# Switches.net
KiCad netlist of a schematic drawn in Altium Designer
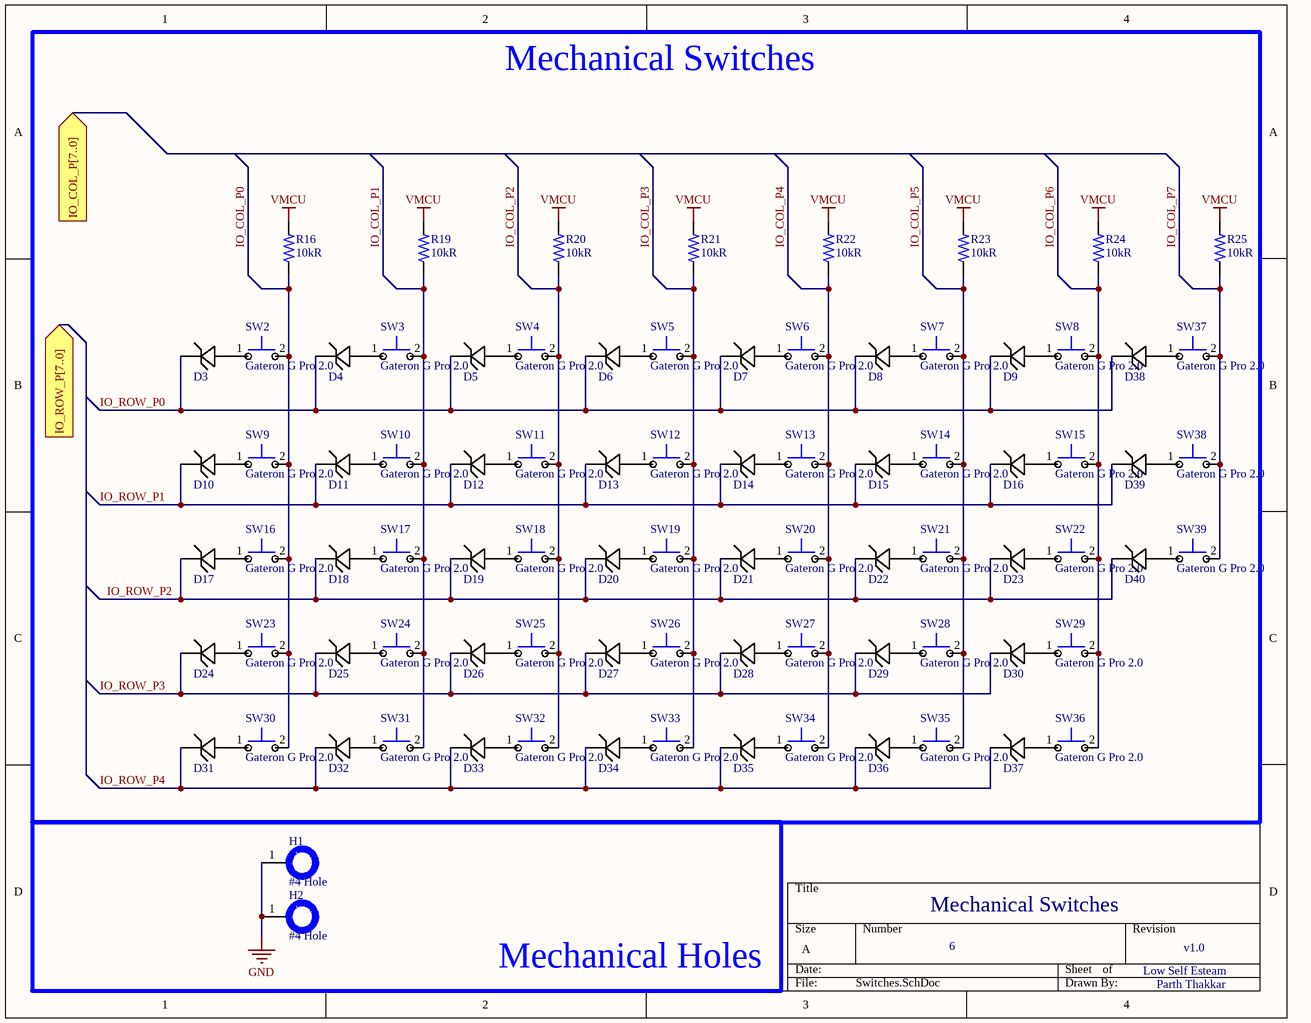
[diagram p0: Switches.SchDoc]

(export (version "E")
  (design (tool "Eeschema 10.0.6"))
  (components
    (comp (ref "D3")
      (value "Diode Schottky")
      (footprint "Diode Schottky")
      (description "Rectifier Diode, Schottky, 2 Element, 0.2A, 30V V(RRM), Silicon")
      (fields (field (name "MANUFACTURER") "Good-Ark") (field (name "MANUFACTURER PART NUMBER") "BAT54C"))
      (libsource (lib "Keyboard_parts") (part "Diode Schottky"))
    )
    (comp (ref "D4")
      (value "Diode Schottky")
      (footprint "Diode Schottky")
      (description "Rectifier Diode, Schottky, 2 Element, 0.2A, 30V V(RRM), Silicon")
      (fields (field (name "MANUFACTURER") "Good-Ark") (field (name "MANUFACTURER PART NUMBER") "BAT54C"))
      (libsource (lib "Keyboard_parts") (part "Diode Schottky"))
    )
    (comp (ref "D5")
      (value "Diode Schottky")
      (footprint "Diode Schottky")
      (description "Rectifier Diode, Schottky, 2 Element, 0.2A, 30V V(RRM), Silicon")
      (fields (field (name "MANUFACTURER") "Good-Ark") (field (name "MANUFACTURER PART NUMBER") "BAT54C"))
      (libsource (lib "Keyboard_parts") (part "Diode Schottky"))
    )
    (comp (ref "D6")
      (value "Diode Schottky")
      (footprint "Diode Schottky")
      (description "Rectifier Diode, Schottky, 2 Element, 0.2A, 30V V(RRM), Silicon")
      (fields (field (name "MANUFACTURER") "Good-Ark") (field (name "MANUFACTURER PART NUMBER") "BAT54C"))
      (libsource (lib "Keyboard_parts") (part "Diode Schottky"))
    )
    (comp (ref "D7")
      (value "Diode Schottky")
      (footprint "Diode Schottky")
      (description "Rectifier Diode, Schottky, 2 Element, 0.2A, 30V V(RRM), Silicon")
      (fields (field (name "MANUFACTURER") "Good-Ark") (field (name "MANUFACTURER PART NUMBER") "BAT54C"))
      (libsource (lib "Keyboard_parts") (part "Diode Schottky"))
    )
    (comp (ref "D8")
      (value "Diode Schottky")
      (footprint "Diode Schottky")
      (description "Rectifier Diode, Schottky, 2 Element, 0.2A, 30V V(RRM), Silicon")
      (fields (field (name "MANUFACTURER") "Good-Ark") (field (name "MANUFACTURER PART NUMBER") "BAT54C"))
      (libsource (lib "Keyboard_parts") (part "Diode Schottky"))
    )
    (comp (ref "D9")
      (value "Diode Schottky")
      (footprint "Diode Schottky")
      (description "Rectifier Diode, Schottky, 2 Element, 0.2A, 30V V(RRM), Silicon")
      (fields (field (name "MANUFACTURER") "Good-Ark") (field (name "MANUFACTURER PART NUMBER") "BAT54C"))
      (libsource (lib "Keyboard_parts") (part "Diode Schottky"))
    )
    (comp (ref "D10")
      (value "Diode Schottky")
      (footprint "Diode Schottky")
      (description "Rectifier Diode, Schottky, 2 Element, 0.2A, 30V V(RRM), Silicon")
      (fields (field (name "MANUFACTURER") "Good-Ark") (field (name "MANUFACTURER PART NUMBER") "BAT54C"))
      (libsource (lib "Keyboard_parts") (part "Diode Schottky"))
    )
    (comp (ref "D11")
      (value "Diode Schottky")
      (footprint "Diode Schottky")
      (description "Rectifier Diode, Schottky, 2 Element, 0.2A, 30V V(RRM), Silicon")
      (fields (field (name "MANUFACTURER") "Good-Ark") (field (name "MANUFACTURER PART NUMBER") "BAT54C"))
      (libsource (lib "Keyboard_parts") (part "Diode Schottky"))
    )
    (comp (ref "D12")
      (value "Diode Schottky")
      (footprint "Diode Schottky")
      (description "Rectifier Diode, Schottky, 2 Element, 0.2A, 30V V(RRM), Silicon")
      (fields (field (name "MANUFACTURER") "Good-Ark") (field (name "MANUFACTURER PART NUMBER") "BAT54C"))
      (libsource (lib "Keyboard_parts") (part "Diode Schottky"))
    )
    (comp (ref "D13")
      (value "Diode Schottky")
      (footprint "Diode Schottky")
      (description "Rectifier Diode, Schottky, 2 Element, 0.2A, 30V V(RRM), Silicon")
      (fields (field (name "MANUFACTURER") "Good-Ark") (field (name "MANUFACTURER PART NUMBER") "BAT54C"))
      (libsource (lib "Keyboard_parts") (part "Diode Schottky"))
    )
    (comp (ref "D14")
      (value "Diode Schottky")
      (footprint "Diode Schottky")
      (description "Rectifier Diode, Schottky, 2 Element, 0.2A, 30V V(RRM), Silicon")
      (fields (field (name "MANUFACTURER") "Good-Ark") (field (name "MANUFACTURER PART NUMBER") "BAT54C"))
      (libsource (lib "Keyboard_parts") (part "Diode Schottky"))
    )
    (comp (ref "D15")
      (value "Diode Schottky")
      (footprint "Diode Schottky")
      (description "Rectifier Diode, Schottky, 2 Element, 0.2A, 30V V(RRM), Silicon")
      (fields (field (name "MANUFACTURER") "Good-Ark") (field (name "MANUFACTURER PART NUMBER") "BAT54C"))
      (libsource (lib "Keyboard_parts") (part "Diode Schottky"))
    )
    (comp (ref "D16")
      (value "Diode Schottky")
      (footprint "Diode Schottky")
      (description "Rectifier Diode, Schottky, 2 Element, 0.2A, 30V V(RRM), Silicon")
      (fields (field (name "MANUFACTURER") "Good-Ark") (field (name "MANUFACTURER PART NUMBER") "BAT54C"))
      (libsource (lib "Keyboard_parts") (part "Diode Schottky"))
    )
    (comp (ref "D17")
      (value "Diode Schottky")
      (footprint "Diode Schottky")
      (description "Rectifier Diode, Schottky, 2 Element, 0.2A, 30V V(RRM), Silicon")
      (fields (field (name "MANUFACTURER") "Good-Ark") (field (name "MANUFACTURER PART NUMBER") "BAT54C"))
      (libsource (lib "Keyboard_parts") (part "Diode Schottky"))
    )
    (comp (ref "D18")
      (value "Diode Schottky")
      (footprint "Diode Schottky")
      (description "Rectifier Diode, Schottky, 2 Element, 0.2A, 30V V(RRM), Silicon")
      (fields (field (name "MANUFACTURER") "Good-Ark") (field (name "MANUFACTURER PART NUMBER") "BAT54C"))
      (libsource (lib "Keyboard_parts") (part "Diode Schottky"))
    )
    (comp (ref "D19")
      (value "Diode Schottky")
      (footprint "Diode Schottky")
      (description "Rectifier Diode, Schottky, 2 Element, 0.2A, 30V V(RRM), Silicon")
      (fields (field (name "MANUFACTURER") "Good-Ark") (field (name "MANUFACTURER PART NUMBER") "BAT54C"))
      (libsource (lib "Keyboard_parts") (part "Diode Schottky"))
    )
    (comp (ref "D20")
      (value "Diode Schottky")
      (footprint "Diode Schottky")
      (description "Rectifier Diode, Schottky, 2 Element, 0.2A, 30V V(RRM), Silicon")
      (fields (field (name "MANUFACTURER") "Good-Ark") (field (name "MANUFACTURER PART NUMBER") "BAT54C"))
      (libsource (lib "Keyboard_parts") (part "Diode Schottky"))
    )
    (comp (ref "D21")
      (value "Diode Schottky")
      (footprint "Diode Schottky")
      (description "Rectifier Diode, Schottky, 2 Element, 0.2A, 30V V(RRM), Silicon")
      (fields (field (name "MANUFACTURER") "Good-Ark") (field (name "MANUFACTURER PART NUMBER") "BAT54C"))
      (libsource (lib "Keyboard_parts") (part "Diode Schottky"))
    )
    (comp (ref "D22")
      (value "Diode Schottky")
      (footprint "Diode Schottky")
      (description "Rectifier Diode, Schottky, 2 Element, 0.2A, 30V V(RRM), Silicon")
      (fields (field (name "MANUFACTURER") "Good-Ark") (field (name "MANUFACTURER PART NUMBER") "BAT54C"))
      (libsource (lib "Keyboard_parts") (part "Diode Schottky"))
    )
    (comp (ref "D23")
      (value "Diode Schottky")
      (footprint "Diode Schottky")
      (description "Rectifier Diode, Schottky, 2 Element, 0.2A, 30V V(RRM), Silicon")
      (fields (field (name "MANUFACTURER") "Good-Ark") (field (name "MANUFACTURER PART NUMBER") "BAT54C"))
      (libsource (lib "Keyboard_parts") (part "Diode Schottky"))
    )
    (comp (ref "D24")
      (value "Diode Schottky")
      (footprint "Diode Schottky")
      (description "Rectifier Diode, Schottky, 2 Element, 0.2A, 30V V(RRM), Silicon")
      (fields (field (name "MANUFACTURER") "Good-Ark") (field (name "MANUFACTURER PART NUMBER") "BAT54C"))
      (libsource (lib "Keyboard_parts") (part "Diode Schottky"))
    )
    (comp (ref "D25")
      (value "Diode Schottky")
      (footprint "Diode Schottky")
      (description "Rectifier Diode, Schottky, 2 Element, 0.2A, 30V V(RRM), Silicon")
      (fields (field (name "MANUFACTURER") "Good-Ark") (field (name "MANUFACTURER PART NUMBER") "BAT54C"))
      (libsource (lib "Keyboard_parts") (part "Diode Schottky"))
    )
    (comp (ref "D26")
      (value "Diode Schottky")
      (footprint "Diode Schottky")
      (description "Rectifier Diode, Schottky, 2 Element, 0.2A, 30V V(RRM), Silicon")
      (fields (field (name "MANUFACTURER") "Good-Ark") (field (name "MANUFACTURER PART NUMBER") "BAT54C"))
      (libsource (lib "Keyboard_parts") (part "Diode Schottky"))
    )
    (comp (ref "D27")
      (value "Diode Schottky")
      (footprint "Diode Schottky")
      (description "Rectifier Diode, Schottky, 2 Element, 0.2A, 30V V(RRM), Silicon")
      (fields (field (name "MANUFACTURER") "Good-Ark") (field (name "MANUFACTURER PART NUMBER") "BAT54C"))
      (libsource (lib "Keyboard_parts") (part "Diode Schottky"))
    )
    (comp (ref "D28")
      (value "Diode Schottky")
      (footprint "Diode Schottky")
      (description "Rectifier Diode, Schottky, 2 Element, 0.2A, 30V V(RRM), Silicon")
      (fields (field (name "MANUFACTURER") "Good-Ark") (field (name "MANUFACTURER PART NUMBER") "BAT54C"))
      (libsource (lib "Keyboard_parts") (part "Diode Schottky"))
    )
    (comp (ref "D29")
      (value "Diode Schottky")
      (footprint "Diode Schottky")
      (description "Rectifier Diode, Schottky, 2 Element, 0.2A, 30V V(RRM), Silicon")
      (fields (field (name "MANUFACTURER") "Good-Ark") (field (name "MANUFACTURER PART NUMBER") "BAT54C"))
      (libsource (lib "Keyboard_parts") (part "Diode Schottky"))
    )
    (comp (ref "D30")
      (value "Diode Schottky")
      (footprint "Diode Schottky")
      (description "Rectifier Diode, Schottky, 2 Element, 0.2A, 30V V(RRM), Silicon")
      (fields (field (name "MANUFACTURER") "Good-Ark") (field (name "MANUFACTURER PART NUMBER") "BAT54C"))
      (libsource (lib "Keyboard_parts") (part "Diode Schottky"))
    )
    (comp (ref "D31")
      (value "Diode Schottky")
      (footprint "Diode Schottky")
      (description "Rectifier Diode, Schottky, 2 Element, 0.2A, 30V V(RRM), Silicon")
      (fields (field (name "MANUFACTURER") "Good-Ark") (field (name "MANUFACTURER PART NUMBER") "BAT54C"))
      (libsource (lib "Keyboard_parts") (part "Diode Schottky"))
    )
    (comp (ref "D32")
      (value "Diode Schottky")
      (footprint "Diode Schottky")
      (description "Rectifier Diode, Schottky, 2 Element, 0.2A, 30V V(RRM), Silicon")
      (fields (field (name "MANUFACTURER") "Good-Ark") (field (name "MANUFACTURER PART NUMBER") "BAT54C"))
      (libsource (lib "Keyboard_parts") (part "Diode Schottky"))
    )
    (comp (ref "D33")
      (value "Diode Schottky")
      (footprint "Diode Schottky")
      (description "Rectifier Diode, Schottky, 2 Element, 0.2A, 30V V(RRM), Silicon")
      (fields (field (name "MANUFACTURER") "Good-Ark") (field (name "MANUFACTURER PART NUMBER") "BAT54C"))
      (libsource (lib "Keyboard_parts") (part "Diode Schottky"))
    )
    (comp (ref "D34")
      (value "Diode Schottky")
      (footprint "Diode Schottky")
      (description "Rectifier Diode, Schottky, 2 Element, 0.2A, 30V V(RRM), Silicon")
      (fields (field (name "MANUFACTURER") "Good-Ark") (field (name "MANUFACTURER PART NUMBER") "BAT54C"))
      (libsource (lib "Keyboard_parts") (part "Diode Schottky"))
    )
    (comp (ref "D35")
      (value "Diode Schottky")
      (footprint "Diode Schottky")
      (description "Rectifier Diode, Schottky, 2 Element, 0.2A, 30V V(RRM), Silicon")
      (fields (field (name "MANUFACTURER") "Good-Ark") (field (name "MANUFACTURER PART NUMBER") "BAT54C"))
      (libsource (lib "Keyboard_parts") (part "Diode Schottky"))
    )
    (comp (ref "D36")
      (value "Diode Schottky")
      (footprint "Diode Schottky")
      (description "Rectifier Diode, Schottky, 2 Element, 0.2A, 30V V(RRM), Silicon")
      (fields (field (name "MANUFACTURER") "Good-Ark") (field (name "MANUFACTURER PART NUMBER") "BAT54C"))
      (libsource (lib "Keyboard_parts") (part "Diode Schottky"))
    )
    (comp (ref "D37")
      (value "Diode Schottky")
      (footprint "Diode Schottky")
      (description "Rectifier Diode, Schottky, 2 Element, 0.2A, 30V V(RRM), Silicon")
      (fields (field (name "MANUFACTURER") "Good-Ark") (field (name "MANUFACTURER PART NUMBER") "BAT54C"))
      (libsource (lib "Keyboard_parts") (part "Diode Schottky"))
    )
    (comp (ref "D38")
      (value "Diode Schottky")
      (footprint "Diode Schottky")
      (description "Rectifier Diode, Schottky, 2 Element, 0.2A, 30V V(RRM), Silicon")
      (fields (field (name "MANUFACTURER") "Good-Ark") (field (name "MANUFACTURER PART NUMBER") "BAT54C"))
      (libsource (lib "Keyboard_parts") (part "Diode Schottky"))
    )
    (comp (ref "D39")
      (value "Diode Schottky")
      (footprint "Diode Schottky")
      (description "Rectifier Diode, Schottky, 2 Element, 0.2A, 30V V(RRM), Silicon")
      (fields (field (name "MANUFACTURER") "Good-Ark") (field (name "MANUFACTURER PART NUMBER") "BAT54C"))
      (libsource (lib "Keyboard_parts") (part "Diode Schottky"))
    )
    (comp (ref "D40")
      (value "Diode Schottky")
      (footprint "Diode Schottky")
      (description "Rectifier Diode, Schottky, 2 Element, 0.2A, 30V V(RRM), Silicon")
      (fields (field (name "MANUFACTURER") "Good-Ark") (field (name "MANUFACTURER PART NUMBER") "BAT54C"))
      (libsource (lib "Keyboard_parts") (part "Diode Schottky"))
    )
    (comp (ref "H1") (value "#4 Hole") (footprint "Hole") (libsource (lib "Keyboard_parts") (part "HOLE_#4")))
    (comp (ref "H2") (value "#4 Hole") (footprint "Hole") (libsource (lib "Keyboard_parts") (part "HOLE_#4")))
    (comp (ref "R16")
      (value "10kR")
      (footprint "Resistor 0603")
      (fields
        (field (name "MANUFACTURER") "Yageo")
        (field (name "MANUFACTURER PART NUMBER") "RC0603FR-0710KL")
        (field (name "TOLERANCE") "1%")
      )
      (libsource (lib "Keyboard_parts") (part "RES 10K 0603"))
    )
    (comp (ref "R19")
      (value "10kR")
      (footprint "Resistor 0603")
      (fields
        (field (name "MANUFACTURER") "Yageo")
        (field (name "MANUFACTURER PART NUMBER") "RC0603FR-0710KL")
        (field (name "TOLERANCE") "1%")
      )
      (libsource (lib "Keyboard_parts") (part "RES 10K 0603"))
    )
    (comp (ref "R20")
      (value "10kR")
      (footprint "Resistor 0603")
      (fields
        (field (name "MANUFACTURER") "Yageo")
        (field (name "MANUFACTURER PART NUMBER") "RC0603FR-0710KL")
        (field (name "TOLERANCE") "1%")
      )
      (libsource (lib "Keyboard_parts") (part "RES 10K 0603"))
    )
    (comp (ref "R21")
      (value "10kR")
      (footprint "Resistor 0603")
      (fields
        (field (name "MANUFACTURER") "Yageo")
        (field (name "MANUFACTURER PART NUMBER") "RC0603FR-0710KL")
        (field (name "TOLERANCE") "1%")
      )
      (libsource (lib "Keyboard_parts") (part "RES 10K 0603"))
    )
    (comp (ref "R22")
      (value "10kR")
      (footprint "Resistor 0603")
      (fields
        (field (name "MANUFACTURER") "Yageo")
        (field (name "MANUFACTURER PART NUMBER") "RC0603FR-0710KL")
        (field (name "TOLERANCE") "1%")
      )
      (libsource (lib "Keyboard_parts") (part "RES 10K 0603"))
    )
    (comp (ref "R23")
      (value "10kR")
      (footprint "Resistor 0603")
      (fields
        (field (name "MANUFACTURER") "Yageo")
        (field (name "MANUFACTURER PART NUMBER") "RC0603FR-0710KL")
        (field (name "TOLERANCE") "1%")
      )
      (libsource (lib "Keyboard_parts") (part "RES 10K 0603"))
    )
    (comp (ref "R24")
      (value "10kR")
      (footprint "Resistor 0603")
      (fields
        (field (name "MANUFACTURER") "Yageo")
        (field (name "MANUFACTURER PART NUMBER") "RC0603FR-0710KL")
        (field (name "TOLERANCE") "1%")
      )
      (libsource (lib "Keyboard_parts") (part "RES 10K 0603"))
    )
    (comp (ref "R25")
      (value "10kR")
      (footprint "Resistor 0603")
      (fields
        (field (name "MANUFACTURER") "Yageo")
        (field (name "MANUFACTURER PART NUMBER") "RC0603FR-0710KL")
        (field (name "TOLERANCE") "1%")
      )
      (libsource (lib "Keyboard_parts") (part "RES 10K 0603"))
    )
    (comp (ref "SW2")
      (value "Gateron G Pro 2.0")
      (footprint "Mechanical Switch")
      (description "Gateron G Pro 2.0, The 3-Pin switches are compatible with any 3-Pin/5-Pin MX mechanical keyboard")
      (libsource (lib "Keyboard_parts") (part "Gateron G Pro 2.0"))
    )
    (comp (ref "SW3")
      (value "Gateron G Pro 2.0")
      (footprint "Mechanical Switch")
      (description "Gateron G Pro 2.0, The 3-Pin switches are compatible with any 3-Pin/5-Pin MX mechanical keyboard")
      (libsource (lib "Keyboard_parts") (part "Gateron G Pro 2.0"))
    )
    (comp (ref "SW4")
      (value "Gateron G Pro 2.0")
      (footprint "Mechanical Switch")
      (description "Gateron G Pro 2.0, The 3-Pin switches are compatible with any 3-Pin/5-Pin MX mechanical keyboard")
      (libsource (lib "Keyboard_parts") (part "Gateron G Pro 2.0"))
    )
    (comp (ref "SW5")
      (value "Gateron G Pro 2.0")
      (footprint "Mechanical Switch")
      (description "Gateron G Pro 2.0, The 3-Pin switches are compatible with any 3-Pin/5-Pin MX mechanical keyboard")
      (libsource (lib "Keyboard_parts") (part "Gateron G Pro 2.0"))
    )
    (comp (ref "SW6")
      (value "Gateron G Pro 2.0")
      (footprint "Mechanical Switch")
      (description "Gateron G Pro 2.0, The 3-Pin switches are compatible with any 3-Pin/5-Pin MX mechanical keyboard")
      (libsource (lib "Keyboard_parts") (part "Gateron G Pro 2.0"))
    )
    (comp (ref "SW7")
      (value "Gateron G Pro 2.0")
      (footprint "Mechanical Switch")
      (description "Gateron G Pro 2.0, The 3-Pin switches are compatible with any 3-Pin/5-Pin MX mechanical keyboard")
      (libsource (lib "Keyboard_parts") (part "Gateron G Pro 2.0"))
    )
    (comp (ref "SW8")
      (value "Gateron G Pro 2.0")
      (footprint "Mechanical Switch")
      (description "Gateron G Pro 2.0, The 3-Pin switches are compatible with any 3-Pin/5-Pin MX mechanical keyboard")
      (libsource (lib "Keyboard_parts") (part "Gateron G Pro 2.0"))
    )
    (comp (ref "SW9")
      (value "Gateron G Pro 2.0")
      (footprint "Mechanical Switch")
      (description "Gateron G Pro 2.0, The 3-Pin switches are compatible with any 3-Pin/5-Pin MX mechanical keyboard")
      (libsource (lib "Keyboard_parts") (part "Gateron G Pro 2.0"))
    )
    (comp (ref "SW10")
      (value "Gateron G Pro 2.0")
      (footprint "Mechanical Switch")
      (description "Gateron G Pro 2.0, The 3-Pin switches are compatible with any 3-Pin/5-Pin MX mechanical keyboard")
      (libsource (lib "Keyboard_parts") (part "Gateron G Pro 2.0"))
    )
    (comp (ref "SW11")
      (value "Gateron G Pro 2.0")
      (footprint "Mechanical Switch")
      (description "Gateron G Pro 2.0, The 3-Pin switches are compatible with any 3-Pin/5-Pin MX mechanical keyboard")
      (libsource (lib "Keyboard_parts") (part "Gateron G Pro 2.0"))
    )
    (comp (ref "SW12")
      (value "Gateron G Pro 2.0")
      (footprint "Mechanical Switch")
      (description "Gateron G Pro 2.0, The 3-Pin switches are compatible with any 3-Pin/5-Pin MX mechanical keyboard")
      (libsource (lib "Keyboard_parts") (part "Gateron G Pro 2.0"))
    )
    (comp (ref "SW13")
      (value "Gateron G Pro 2.0")
      (footprint "Mechanical Switch")
      (description "Gateron G Pro 2.0, The 3-Pin switches are compatible with any 3-Pin/5-Pin MX mechanical keyboard")
      (libsource (lib "Keyboard_parts") (part "Gateron G Pro 2.0"))
    )
    (comp (ref "SW14")
      (value "Gateron G Pro 2.0")
      (footprint "Mechanical Switch")
      (description "Gateron G Pro 2.0, The 3-Pin switches are compatible with any 3-Pin/5-Pin MX mechanical keyboard")
      (libsource (lib "Keyboard_parts") (part "Gateron G Pro 2.0"))
    )
    (comp (ref "SW15")
      (value "Gateron G Pro 2.0")
      (footprint "Mechanical Switch")
      (description "Gateron G Pro 2.0, The 3-Pin switches are compatible with any 3-Pin/5-Pin MX mechanical keyboard")
      (libsource (lib "Keyboard_parts") (part "Gateron G Pro 2.0"))
    )
    (comp (ref "SW16")
      (value "Gateron G Pro 2.0")
      (footprint "Mechanical Switch")
      (description "Gateron G Pro 2.0, The 3-Pin switches are compatible with any 3-Pin/5-Pin MX mechanical keyboard")
      (libsource (lib "Keyboard_parts") (part "Gateron G Pro 2.0"))
    )
    (comp (ref "SW17")
      (value "Gateron G Pro 2.0")
      (footprint "Mechanical Switch")
      (description "Gateron G Pro 2.0, The 3-Pin switches are compatible with any 3-Pin/5-Pin MX mechanical keyboard")
      (libsource (lib "Keyboard_parts") (part "Gateron G Pro 2.0"))
    )
    (comp (ref "SW18")
      (value "Gateron G Pro 2.0")
      (footprint "Mechanical Switch")
      (description "Gateron G Pro 2.0, The 3-Pin switches are compatible with any 3-Pin/5-Pin MX mechanical keyboard")
      (libsource (lib "Keyboard_parts") (part "Gateron G Pro 2.0"))
    )
    (comp (ref "SW19")
      (value "Gateron G Pro 2.0")
      (footprint "Mechanical Switch")
      (description "Gateron G Pro 2.0, The 3-Pin switches are compatible with any 3-Pin/5-Pin MX mechanical keyboard")
      (libsource (lib "Keyboard_parts") (part "Gateron G Pro 2.0"))
    )
    (comp (ref "SW20")
      (value "Gateron G Pro 2.0")
      (footprint "Mechanical Switch")
      (description "Gateron G Pro 2.0, The 3-Pin switches are compatible with any 3-Pin/5-Pin MX mechanical keyboard")
      (libsource (lib "Keyboard_parts") (part "Gateron G Pro 2.0"))
    )
    (comp (ref "SW21")
      (value "Gateron G Pro 2.0")
      (footprint "Mechanical Switch")
      (description "Gateron G Pro 2.0, The 3-Pin switches are compatible with any 3-Pin/5-Pin MX mechanical keyboard")
      (libsource (lib "Keyboard_parts") (part "Gateron G Pro 2.0"))
    )
    (comp (ref "SW22")
      (value "Gateron G Pro 2.0")
      (footprint "Mechanical Switch")
      (description "Gateron G Pro 2.0, The 3-Pin switches are compatible with any 3-Pin/5-Pin MX mechanical keyboard")
      (libsource (lib "Keyboard_parts") (part "Gateron G Pro 2.0"))
    )
    (comp (ref "SW23")
      (value "Gateron G Pro 2.0")
      (footprint "Mechanical Switch")
      (description "Gateron G Pro 2.0, The 3-Pin switches are compatible with any 3-Pin/5-Pin MX mechanical keyboard")
      (libsource (lib "Keyboard_parts") (part "Gateron G Pro 2.0"))
    )
    (comp (ref "SW24")
      (value "Gateron G Pro 2.0")
      (footprint "Mechanical Switch")
      (description "Gateron G Pro 2.0, The 3-Pin switches are compatible with any 3-Pin/5-Pin MX mechanical keyboard")
      (libsource (lib "Keyboard_parts") (part "Gateron G Pro 2.0"))
    )
    (comp (ref "SW25")
      (value "Gateron G Pro 2.0")
      (footprint "Mechanical Switch")
      (description "Gateron G Pro 2.0, The 3-Pin switches are compatible with any 3-Pin/5-Pin MX mechanical keyboard")
      (libsource (lib "Keyboard_parts") (part "Gateron G Pro 2.0"))
    )
    (comp (ref "SW26")
      (value "Gateron G Pro 2.0")
      (footprint "Mechanical Switch")
      (description "Gateron G Pro 2.0, The 3-Pin switches are compatible with any 3-Pin/5-Pin MX mechanical keyboard")
      (libsource (lib "Keyboard_parts") (part "Gateron G Pro 2.0"))
    )
    (comp (ref "SW27")
      (value "Gateron G Pro 2.0")
      (footprint "Mechanical Switch")
      (description "Gateron G Pro 2.0, The 3-Pin switches are compatible with any 3-Pin/5-Pin MX mechanical keyboard")
      (libsource (lib "Keyboard_parts") (part "Gateron G Pro 2.0"))
    )
    (comp (ref "SW28")
      (value "Gateron G Pro 2.0")
      (footprint "Mechanical Switch")
      (description "Gateron G Pro 2.0, The 3-Pin switches are compatible with any 3-Pin/5-Pin MX mechanical keyboard")
      (libsource (lib "Keyboard_parts") (part "Gateron G Pro 2.0"))
    )
    (comp (ref "SW29")
      (value "Gateron G Pro 2.0")
      (footprint "Mechanical Switch")
      (description "Gateron G Pro 2.0, The 3-Pin switches are compatible with any 3-Pin/5-Pin MX mechanical keyboard")
      (libsource (lib "Keyboard_parts") (part "Gateron G Pro 2.0"))
    )
    (comp (ref "SW30")
      (value "Gateron G Pro 2.0")
      (footprint "Mechanical Switch")
      (description "Gateron G Pro 2.0, The 3-Pin switches are compatible with any 3-Pin/5-Pin MX mechanical keyboard")
      (libsource (lib "Keyboard_parts") (part "Gateron G Pro 2.0"))
    )
    (comp (ref "SW31")
      (value "Gateron G Pro 2.0")
      (footprint "Mechanical Switch")
      (description "Gateron G Pro 2.0, The 3-Pin switches are compatible with any 3-Pin/5-Pin MX mechanical keyboard")
      (libsource (lib "Keyboard_parts") (part "Gateron G Pro 2.0"))
    )
    (comp (ref "SW32")
      (value "Gateron G Pro 2.0")
      (footprint "Mechanical Switch")
      (description "Gateron G Pro 2.0, The 3-Pin switches are compatible with any 3-Pin/5-Pin MX mechanical keyboard")
      (libsource (lib "Keyboard_parts") (part "Gateron G Pro 2.0"))
    )
    (comp (ref "SW33")
      (value "Gateron G Pro 2.0")
      (footprint "Mechanical Switch")
      (description "Gateron G Pro 2.0, The 3-Pin switches are compatible with any 3-Pin/5-Pin MX mechanical keyboard")
      (libsource (lib "Keyboard_parts") (part "Gateron G Pro 2.0"))
    )
    (comp (ref "SW34")
      (value "Gateron G Pro 2.0")
      (footprint "Mechanical Switch")
      (description "Gateron G Pro 2.0, The 3-Pin switches are compatible with any 3-Pin/5-Pin MX mechanical keyboard")
      (libsource (lib "Keyboard_parts") (part "Gateron G Pro 2.0"))
    )
    (comp (ref "SW35")
      (value "Gateron G Pro 2.0")
      (footprint "Mechanical Switch")
      (description "Gateron G Pro 2.0, The 3-Pin switches are compatible with any 3-Pin/5-Pin MX mechanical keyboard")
      (libsource (lib "Keyboard_parts") (part "Gateron G Pro 2.0"))
    )
    (comp (ref "SW36")
      (value "Gateron G Pro 2.0")
      (footprint "Mechanical Switch")
      (description "Gateron G Pro 2.0, The 3-Pin switches are compatible with any 3-Pin/5-Pin MX mechanical keyboard")
      (libsource (lib "Keyboard_parts") (part "Gateron G Pro 2.0"))
    )
    (comp (ref "SW37")
      (value "Gateron G Pro 2.0")
      (footprint "Mechanical Switch")
      (description "Gateron G Pro 2.0, The 3-Pin switches are compatible with any 3-Pin/5-Pin MX mechanical keyboard")
      (libsource (lib "Keyboard_parts") (part "Gateron G Pro 2.0"))
    )
    (comp (ref "SW38")
      (value "Gateron G Pro 2.0")
      (footprint "Mechanical Switch")
      (description "Gateron G Pro 2.0, The 3-Pin switches are compatible with any 3-Pin/5-Pin MX mechanical keyboard")
      (libsource (lib "Keyboard_parts") (part "Gateron G Pro 2.0"))
    )
    (comp (ref "SW39")
      (value "Gateron G Pro 2.0")
      (footprint "Mechanical Switch")
      (description "Gateron G Pro 2.0, The 3-Pin switches are compatible with any 3-Pin/5-Pin MX mechanical keyboard")
      (libsource (lib "Keyboard_parts") (part "Gateron G Pro 2.0"))
    )
  )
  (nets
    (net (code "4") (name "/IO_COL_P0") (class "Default")
      (node (ref "R16") (pin "1") (pinfunction "1_1") (pintype "passive"))
      (node (ref "SW16") (pin "2") (pinfunction "2_2") (pintype "passive"))
      (node (ref "SW2") (pin "2") (pinfunction "2_2") (pintype "passive"))
      (node (ref "SW23") (pin "2") (pinfunction "2_2") (pintype "passive"))
      (node (ref "SW30") (pin "2") (pinfunction "2_2") (pintype "passive"))
      (node (ref "SW9") (pin "2") (pinfunction "2_2") (pintype "passive"))
    )
    (net (code "5") (name "/IO_COL_P1") (class "Default")
      (node (ref "R19") (pin "1") (pinfunction "1_1") (pintype "passive"))
      (node (ref "SW10") (pin "2") (pinfunction "2_2") (pintype "passive"))
      (node (ref "SW17") (pin "2") (pinfunction "2_2") (pintype "passive"))
      (node (ref "SW24") (pin "2") (pinfunction "2_2") (pintype "passive"))
      (node (ref "SW3") (pin "2") (pinfunction "2_2") (pintype "passive"))
      (node (ref "SW31") (pin "2") (pinfunction "2_2") (pintype "passive"))
    )
    (net (code "6") (name "/IO_COL_P2") (class "Default")
      (node (ref "R20") (pin "1") (pinfunction "1_1") (pintype "passive"))
      (node (ref "SW11") (pin "2") (pinfunction "2_2") (pintype "passive"))
      (node (ref "SW18") (pin "2") (pinfunction "2_2") (pintype "passive"))
      (node (ref "SW25") (pin "2") (pinfunction "2_2") (pintype "passive"))
      (node (ref "SW32") (pin "2") (pinfunction "2_2") (pintype "passive"))
      (node (ref "SW4") (pin "2") (pinfunction "2_2") (pintype "passive"))
    )
    (net (code "7") (name "/IO_COL_P3") (class "Default")
      (node (ref "R21") (pin "1") (pinfunction "1_1") (pintype "passive"))
      (node (ref "SW12") (pin "2") (pinfunction "2_2") (pintype "passive"))
      (node (ref "SW19") (pin "2") (pinfunction "2_2") (pintype "passive"))
      (node (ref "SW26") (pin "2") (pinfunction "2_2") (pintype "passive"))
      (node (ref "SW33") (pin "2") (pinfunction "2_2") (pintype "passive"))
      (node (ref "SW5") (pin "2") (pinfunction "2_2") (pintype "passive"))
    )
    (net (code "8") (name "/IO_COL_P4") (class "Default")
      (node (ref "R22") (pin "1") (pinfunction "1_1") (pintype "passive"))
      (node (ref "SW13") (pin "2") (pinfunction "2_2") (pintype "passive"))
      (node (ref "SW20") (pin "2") (pinfunction "2_2") (pintype "passive"))
      (node (ref "SW27") (pin "2") (pinfunction "2_2") (pintype "passive"))
      (node (ref "SW34") (pin "2") (pinfunction "2_2") (pintype "passive"))
      (node (ref "SW6") (pin "2") (pinfunction "2_2") (pintype "passive"))
    )
    (net (code "9") (name "/IO_COL_P5") (class "Default")
      (node (ref "R23") (pin "1") (pinfunction "1_1") (pintype "passive"))
      (node (ref "SW14") (pin "2") (pinfunction "2_2") (pintype "passive"))
      (node (ref "SW21") (pin "2") (pinfunction "2_2") (pintype "passive"))
      (node (ref "SW28") (pin "2") (pinfunction "2_2") (pintype "passive"))
      (node (ref "SW35") (pin "2") (pinfunction "2_2") (pintype "passive"))
      (node (ref "SW7") (pin "2") (pinfunction "2_2") (pintype "passive"))
    )
    (net (code "10") (name "/IO_COL_P6") (class "Default")
      (node (ref "R24") (pin "1") (pinfunction "1_1") (pintype "passive"))
      (node (ref "SW15") (pin "2") (pinfunction "2_2") (pintype "passive"))
      (node (ref "SW22") (pin "2") (pinfunction "2_2") (pintype "passive"))
      (node (ref "SW29") (pin "2") (pinfunction "2_2") (pintype "passive"))
      (node (ref "SW36") (pin "2") (pinfunction "2_2") (pintype "passive"))
      (node (ref "SW8") (pin "2") (pinfunction "2_2") (pintype "passive"))
    )
    (net (code "11") (name "/IO_COL_P7") (class "Default")
      (node (ref "R25") (pin "1") (pinfunction "1_1") (pintype "passive"))
      (node (ref "SW37") (pin "2") (pinfunction "2_2") (pintype "passive"))
      (node (ref "SW38") (pin "2") (pinfunction "2_2") (pintype "passive"))
      (node (ref "SW39") (pin "2") (pinfunction "2_2") (pintype "passive"))
    )
    (net (code "13") (name "/IO_ROW_P0") (class "Default")
      (node (ref "D3") (pin "3") (pinfunction "3_3") (pintype "passive"))
      (node (ref "D38") (pin "3") (pinfunction "3_3") (pintype "passive"))
      (node (ref "D4") (pin "3") (pinfunction "3_3") (pintype "passive"))
      (node (ref "D5") (pin "3") (pinfunction "3_3") (pintype "passive"))
      (node (ref "D6") (pin "3") (pinfunction "3_3") (pintype "passive"))
      (node (ref "D7") (pin "3") (pinfunction "3_3") (pintype "passive"))
      (node (ref "D8") (pin "3") (pinfunction "3_3") (pintype "passive"))
      (node (ref "D9") (pin "3") (pinfunction "3_3") (pintype "passive"))
    )
    (net (code "14") (name "/IO_ROW_P1") (class "Default")
      (node (ref "D10") (pin "3") (pinfunction "3_3") (pintype "passive"))
      (node (ref "D11") (pin "3") (pinfunction "3_3") (pintype "passive"))
      (node (ref "D12") (pin "3") (pinfunction "3_3") (pintype "passive"))
      (node (ref "D13") (pin "3") (pinfunction "3_3") (pintype "passive"))
      (node (ref "D14") (pin "3") (pinfunction "3_3") (pintype "passive"))
      (node (ref "D15") (pin "3") (pinfunction "3_3") (pintype "passive"))
      (node (ref "D16") (pin "3") (pinfunction "3_3") (pintype "passive"))
      (node (ref "D39") (pin "3") (pinfunction "3_3") (pintype "passive"))
    )
    (net (code "15") (name "/IO_ROW_P2") (class "Default")
      (node (ref "D17") (pin "3") (pinfunction "3_3") (pintype "passive"))
      (node (ref "D18") (pin "3") (pinfunction "3_3") (pintype "passive"))
      (node (ref "D19") (pin "3") (pinfunction "3_3") (pintype "passive"))
      (node (ref "D20") (pin "3") (pinfunction "3_3") (pintype "passive"))
      (node (ref "D21") (pin "3") (pinfunction "3_3") (pintype "passive"))
      (node (ref "D22") (pin "3") (pinfunction "3_3") (pintype "passive"))
      (node (ref "D23") (pin "3") (pinfunction "3_3") (pintype "passive"))
      (node (ref "D40") (pin "3") (pinfunction "3_3") (pintype "passive"))
    )
    (net (code "16") (name "/IO_ROW_P3") (class "Default")
      (node (ref "D24") (pin "3") (pinfunction "3_3") (pintype "passive"))
      (node (ref "D25") (pin "3") (pinfunction "3_3") (pintype "passive"))
      (node (ref "D26") (pin "3") (pinfunction "3_3") (pintype "passive"))
      (node (ref "D27") (pin "3") (pinfunction "3_3") (pintype "passive"))
      (node (ref "D28") (pin "3") (pinfunction "3_3") (pintype "passive"))
      (node (ref "D29") (pin "3") (pinfunction "3_3") (pintype "passive"))
      (node (ref "D30") (pin "3") (pinfunction "3_3") (pintype "passive"))
    )
    (net (code "17") (name "/IO_ROW_P4") (class "Default")
      (node (ref "D31") (pin "3") (pinfunction "3_3") (pintype "passive"))
      (node (ref "D32") (pin "3") (pinfunction "3_3") (pintype "passive"))
      (node (ref "D33") (pin "3") (pinfunction "3_3") (pintype "passive"))
      (node (ref "D34") (pin "3") (pinfunction "3_3") (pintype "passive"))
      (node (ref "D35") (pin "3") (pinfunction "3_3") (pintype "passive"))
      (node (ref "D36") (pin "3") (pinfunction "3_3") (pintype "passive"))
      (node (ref "D37") (pin "3") (pinfunction "3_3") (pintype "passive"))
    )
    (net (code "19") (name "GND") (class "Default")
      (node (ref "H1") (pin "1") (pinfunction "1_1") (pintype "passive"))
      (node (ref "H2") (pin "1") (pinfunction "1_1") (pintype "passive"))
    )
    (net (code "20") (name "Net-(D3-Pad1)") (class "Default")
      (node (ref "D3") (pin "1") (pinfunction "1_1") (pintype "passive"))
      (node (ref "SW2") (pin "1") (pinfunction "1_1") (pintype "passive"))
    )
    (net (code "21") (name "Net-(D4-Pad1)") (class "Default")
      (node (ref "D4") (pin "1") (pinfunction "1_1") (pintype "passive"))
      (node (ref "SW3") (pin "1") (pinfunction "1_1") (pintype "passive"))
    )
    (net (code "22") (name "Net-(D5-Pad1)") (class "Default")
      (node (ref "D5") (pin "1") (pinfunction "1_1") (pintype "passive"))
      (node (ref "SW4") (pin "1") (pinfunction "1_1") (pintype "passive"))
    )
    (net (code "23") (name "Net-(D6-Pad1)") (class "Default")
      (node (ref "D6") (pin "1") (pinfunction "1_1") (pintype "passive"))
      (node (ref "SW5") (pin "1") (pinfunction "1_1") (pintype "passive"))
    )
    (net (code "24") (name "Net-(D7-Pad1)") (class "Default")
      (node (ref "D7") (pin "1") (pinfunction "1_1") (pintype "passive"))
      (node (ref "SW6") (pin "1") (pinfunction "1_1") (pintype "passive"))
    )
    (net (code "25") (name "Net-(D8-Pad1)") (class "Default")
      (node (ref "D8") (pin "1") (pinfunction "1_1") (pintype "passive"))
      (node (ref "SW7") (pin "1") (pinfunction "1_1") (pintype "passive"))
    )
    (net (code "26") (name "Net-(D9-Pad1)") (class "Default")
      (node (ref "D9") (pin "1") (pinfunction "1_1") (pintype "passive"))
      (node (ref "SW8") (pin "1") (pinfunction "1_1") (pintype "passive"))
    )
    (net (code "27") (name "Net-(D10-Pad1)") (class "Default")
      (node (ref "D10") (pin "1") (pinfunction "1_1") (pintype "passive"))
      (node (ref "SW9") (pin "1") (pinfunction "1_1") (pintype "passive"))
    )
    (net (code "28") (name "Net-(D11-Pad1)") (class "Default")
      (node (ref "D11") (pin "1") (pinfunction "1_1") (pintype "passive"))
      (node (ref "SW10") (pin "1") (pinfunction "1_1") (pintype "passive"))
    )
    (net (code "29") (name "Net-(D12-Pad1)") (class "Default")
      (node (ref "D12") (pin "1") (pinfunction "1_1") (pintype "passive"))
      (node (ref "SW11") (pin "1") (pinfunction "1_1") (pintype "passive"))
    )
    (net (code "30") (name "Net-(D13-Pad1)") (class "Default")
      (node (ref "D13") (pin "1") (pinfunction "1_1") (pintype "passive"))
      (node (ref "SW12") (pin "1") (pinfunction "1_1") (pintype "passive"))
    )
    (net (code "31") (name "Net-(D14-Pad1)") (class "Default")
      (node (ref "D14") (pin "1") (pinfunction "1_1") (pintype "passive"))
      (node (ref "SW13") (pin "1") (pinfunction "1_1") (pintype "passive"))
    )
    (net (code "32") (name "Net-(D15-Pad1)") (class "Default")
      (node (ref "D15") (pin "1") (pinfunction "1_1") (pintype "passive"))
      (node (ref "SW14") (pin "1") (pinfunction "1_1") (pintype "passive"))
    )
    (net (code "33") (name "Net-(D16-Pad1)") (class "Default")
      (node (ref "D16") (pin "1") (pinfunction "1_1") (pintype "passive"))
      (node (ref "SW15") (pin "1") (pinfunction "1_1") (pintype "passive"))
    )
    (net (code "34") (name "Net-(D17-Pad1)") (class "Default")
      (node (ref "D17") (pin "1") (pinfunction "1_1") (pintype "passive"))
      (node (ref "SW16") (pin "1") (pinfunction "1_1") (pintype "passive"))
    )
    (net (code "35") (name "Net-(D18-Pad1)") (class "Default")
      (node (ref "D18") (pin "1") (pinfunction "1_1") (pintype "passive"))
      (node (ref "SW17") (pin "1") (pinfunction "1_1") (pintype "passive"))
    )
    (net (code "36") (name "Net-(D19-Pad1)") (class "Default")
      (node (ref "D19") (pin "1") (pinfunction "1_1") (pintype "passive"))
      (node (ref "SW18") (pin "1") (pinfunction "1_1") (pintype "passive"))
    )
    (net (code "37") (name "Net-(D20-Pad1)") (class "Default")
      (node (ref "D20") (pin "1") (pinfunction "1_1") (pintype "passive"))
      (node (ref "SW19") (pin "1") (pinfunction "1_1") (pintype "passive"))
    )
    (net (code "38") (name "Net-(D21-Pad1)") (class "Default")
      (node (ref "D21") (pin "1") (pinfunction "1_1") (pintype "passive"))
      (node (ref "SW20") (pin "1") (pinfunction "1_1") (pintype "passive"))
    )
    (net (code "39") (name "Net-(D22-Pad1)") (class "Default")
      (node (ref "D22") (pin "1") (pinfunction "1_1") (pintype "passive"))
      (node (ref "SW21") (pin "1") (pinfunction "1_1") (pintype "passive"))
    )
    (net (code "40") (name "Net-(D23-Pad1)") (class "Default")
      (node (ref "D23") (pin "1") (pinfunction "1_1") (pintype "passive"))
      (node (ref "SW22") (pin "1") (pinfunction "1_1") (pintype "passive"))
    )
    (net (code "41") (name "Net-(D24-Pad1)") (class "Default")
      (node (ref "D24") (pin "1") (pinfunction "1_1") (pintype "passive"))
      (node (ref "SW23") (pin "1") (pinfunction "1_1") (pintype "passive"))
    )
    (net (code "42") (name "Net-(D25-Pad1)") (class "Default")
      (node (ref "D25") (pin "1") (pinfunction "1_1") (pintype "passive"))
      (node (ref "SW24") (pin "1") (pinfunction "1_1") (pintype "passive"))
    )
    (net (code "43") (name "Net-(D26-Pad1)") (class "Default")
      (node (ref "D26") (pin "1") (pinfunction "1_1") (pintype "passive"))
      (node (ref "SW25") (pin "1") (pinfunction "1_1") (pintype "passive"))
    )
    (net (code "44") (name "Net-(D27-Pad1)") (class "Default")
      (node (ref "D27") (pin "1") (pinfunction "1_1") (pintype "passive"))
      (node (ref "SW26") (pin "1") (pinfunction "1_1") (pintype "passive"))
    )
    (net (code "45") (name "Net-(D28-Pad1)") (class "Default")
      (node (ref "D28") (pin "1") (pinfunction "1_1") (pintype "passive"))
      (node (ref "SW27") (pin "1") (pinfunction "1_1") (pintype "passive"))
    )
    (net (code "46") (name "Net-(D29-Pad1)") (class "Default")
      (node (ref "D29") (pin "1") (pinfunction "1_1") (pintype "passive"))
      (node (ref "SW28") (pin "1") (pinfunction "1_1") (pintype "passive"))
    )
    (net (code "47") (name "Net-(D30-Pad1)") (class "Default")
      (node (ref "D30") (pin "1") (pinfunction "1_1") (pintype "passive"))
      (node (ref "SW29") (pin "1") (pinfunction "1_1") (pintype "passive"))
    )
    (net (code "48") (name "Net-(D31-Pad1)") (class "Default")
      (node (ref "D31") (pin "1") (pinfunction "1_1") (pintype "passive"))
      (node (ref "SW30") (pin "1") (pinfunction "1_1") (pintype "passive"))
    )
    (net (code "49") (name "Net-(D32-Pad1)") (class "Default")
      (node (ref "D32") (pin "1") (pinfunction "1_1") (pintype "passive"))
      (node (ref "SW31") (pin "1") (pinfunction "1_1") (pintype "passive"))
    )
    (net (code "50") (name "Net-(D33-Pad1)") (class "Default")
      (node (ref "D33") (pin "1") (pinfunction "1_1") (pintype "passive"))
      (node (ref "SW32") (pin "1") (pinfunction "1_1") (pintype "passive"))
    )
    (net (code "51") (name "Net-(D34-Pad1)") (class "Default")
      (node (ref "D34") (pin "1") (pinfunction "1_1") (pintype "passive"))
      (node (ref "SW33") (pin "1") (pinfunction "1_1") (pintype "passive"))
    )
    (net (code "52") (name "Net-(D35-Pad1)") (class "Default")
      (node (ref "D35") (pin "1") (pinfunction "1_1") (pintype "passive"))
      (node (ref "SW34") (pin "1") (pinfunction "1_1") (pintype "passive"))
    )
    (net (code "53") (name "Net-(D36-Pad1)") (class "Default")
      (node (ref "D36") (pin "1") (pinfunction "1_1") (pintype "passive"))
      (node (ref "SW35") (pin "1") (pinfunction "1_1") (pintype "passive"))
    )
    (net (code "54") (name "Net-(D37-Pad1)") (class "Default")
      (node (ref "D37") (pin "1") (pinfunction "1_1") (pintype "passive"))
      (node (ref "SW36") (pin "1") (pinfunction "1_1") (pintype "passive"))
    )
    (net (code "55") (name "Net-(D38-Pad1)") (class "Default")
      (node (ref "D38") (pin "1") (pinfunction "1_1") (pintype "passive"))
      (node (ref "SW37") (pin "1") (pinfunction "1_1") (pintype "passive"))
    )
    (net (code "56") (name "Net-(D39-Pad1)") (class "Default")
      (node (ref "D39") (pin "1") (pinfunction "1_1") (pintype "passive"))
      (node (ref "SW38") (pin "1") (pinfunction "1_1") (pintype "passive"))
    )
    (net (code "57") (name "Net-(D40-Pad1)") (class "Default")
      (node (ref "D40") (pin "1") (pinfunction "1_1") (pintype "passive"))
      (node (ref "SW39") (pin "1") (pinfunction "1_1") (pintype "passive"))
    )
    (net (code "58") (name "VMCU") (class "Default")
      (node (ref "R16") (pin "2") (pinfunction "2_2") (pintype "passive"))
      (node (ref "R19") (pin "2") (pinfunction "2_2") (pintype "passive"))
      (node (ref "R20") (pin "2") (pinfunction "2_2") (pintype "passive"))
      (node (ref "R21") (pin "2") (pinfunction "2_2") (pintype "passive"))
      (node (ref "R22") (pin "2") (pinfunction "2_2") (pintype "passive"))
      (node (ref "R23") (pin "2") (pinfunction "2_2") (pintype "passive"))
      (node (ref "R24") (pin "2") (pinfunction "2_2") (pintype "passive"))
      (node (ref "R25") (pin "2") (pinfunction "2_2") (pintype "passive"))
    )
  )
)
